# v1.net
KiCad netlist of a schematic drawn in EAGLE
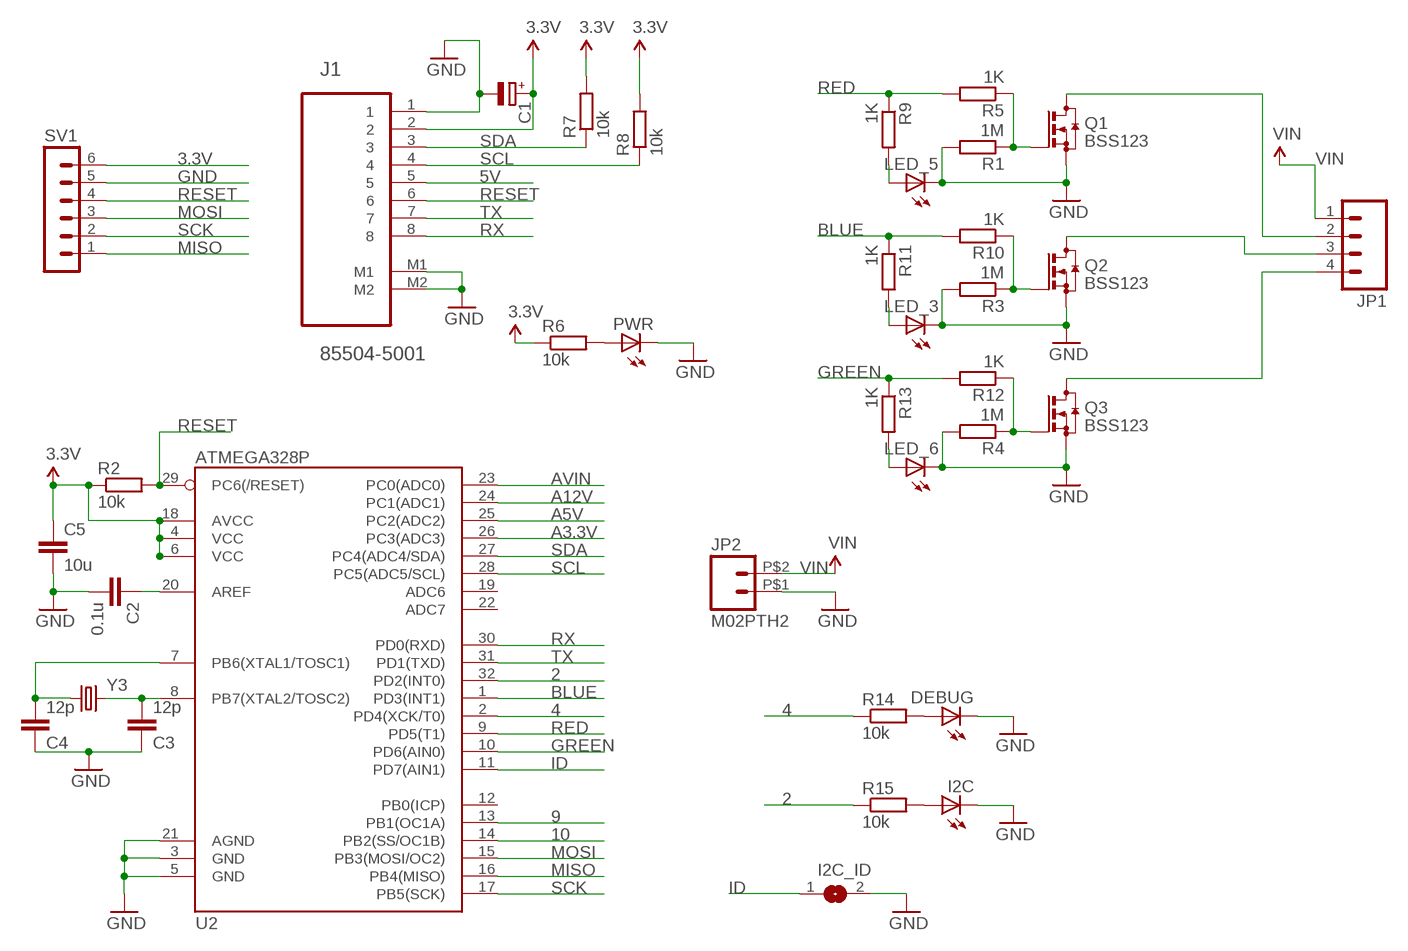
[diagram p0: schematic, sheet 1]

(export (version "E")
  (design (tool "Eeschema 10.0.6"))
  (components
    (comp (ref "C1")
      (value "CPOL-EUE2.5-6")
      (footprint "eagle-import:E2,5-6")
      (libsource (lib "eagle-import") (part "CPOL-EUE2.5-6"))
    )
    (comp (ref "C2")
      (value "0.1u")
      (footprint "eagle-import:C0805")
      (libsource (lib "eagle-import") (part "C-EUC0805"))
    )
    (comp (ref "C3")
      (value "12p")
      (footprint "eagle-import:C0805")
      (libsource (lib "eagle-import") (part "C-EUC0805"))
    )
    (comp (ref "C4")
      (value "12p")
      (footprint "eagle-import:C0805")
      (libsource (lib "eagle-import") (part "C-EUC0805"))
    )
    (comp (ref "C5")
      (value "10u")
      (footprint "eagle-import:C0805")
      (libsource (lib "eagle-import") (part "C-EUC0805"))
    )
    (comp (ref "DEBUG")
      (value "LEDSML0805")
      (footprint "eagle-import:SML0805")
      (libsource (lib "eagle-import") (part "LEDSML0805"))
    )
    (comp (ref "I2C")
      (value "LEDSML0805")
      (footprint "eagle-import:SML0805")
      (libsource (lib "eagle-import") (part "LEDSML0805"))
    )
    (comp (ref "I2C_ID")
      (value "SJ")
      (footprint "eagle-import:SJ")
      (libsource (lib "eagle-import") (part "SJ"))
    )
    (comp (ref "J1")
      (value "85504-5001")
      (footprint "eagle-import:MOLEX_85504-5001")
      (libsource (lib "eagle-import") (part "85504-5001"))
    )
    (comp (ref "JP1")
      (value "M04POLAR")
      (footprint "eagle-import:MOLEX-1X4")
      (libsource (lib "eagle-import") (part "M04POLAR"))
    )
    (comp (ref "JP2")
      (value "M02PTH2")
      (footprint "eagle-import:1X02_BIG")
      (libsource (lib "eagle-import") (part "M02PTH2"))
    )
    (comp (ref "LED_3")
      (value "LEDSML0805")
      (footprint "eagle-import:SML0805")
      (libsource (lib "eagle-import") (part "LEDSML0805"))
    )
    (comp (ref "LED_5")
      (value "LEDSML0805")
      (footprint "eagle-import:SML0805")
      (libsource (lib "eagle-import") (part "LEDSML0805"))
    )
    (comp (ref "LED_6")
      (value "LEDSML0805")
      (footprint "eagle-import:SML0805")
      (libsource (lib "eagle-import") (part "LEDSML0805"))
    )
    (comp (ref "PWR")
      (value "LEDSML0805")
      (footprint "eagle-import:SML0805")
      (libsource (lib "eagle-import") (part "LEDSML0805"))
    )
    (comp (ref "Q1")
      (value "BSS123")
      (footprint "eagle-import:SOT23")
      (libsource (lib "eagle-import") (part "BSS123"))
    )
    (comp (ref "Q2")
      (value "BSS123")
      (footprint "eagle-import:SOT23")
      (libsource (lib "eagle-import") (part "BSS123"))
    )
    (comp (ref "Q3")
      (value "BSS123")
      (footprint "eagle-import:SOT23")
      (libsource (lib "eagle-import") (part "BSS123"))
    )
    (comp (ref "R1")
      (value "1M")
      (footprint "eagle-import:R0805")
      (libsource (lib "eagle-import") (part "R-EU_R0805"))
    )
    (comp (ref "R2")
      (value "10k")
      (footprint "eagle-import:R0805")
      (libsource (lib "eagle-import") (part "R-EU_R0805"))
    )
    (comp (ref "R3")
      (value "1M")
      (footprint "eagle-import:R0805")
      (libsource (lib "eagle-import") (part "R-EU_R0805"))
    )
    (comp (ref "R4")
      (value "1M")
      (footprint "eagle-import:R0805")
      (libsource (lib "eagle-import") (part "R-EU_R0805"))
    )
    (comp (ref "R5")
      (value "1K")
      (footprint "eagle-import:R0805")
      (libsource (lib "eagle-import") (part "R-EU_R0805"))
    )
    (comp (ref "R6")
      (value "10k")
      (footprint "eagle-import:R0805")
      (libsource (lib "eagle-import") (part "R-EU_R0805"))
    )
    (comp (ref "R7")
      (value "10k")
      (footprint "eagle-import:R0805")
      (libsource (lib "eagle-import") (part "R-EU_R0805"))
    )
    (comp (ref "R8")
      (value "10k")
      (footprint "eagle-import:R0805")
      (libsource (lib "eagle-import") (part "R-EU_R0805"))
    )
    (comp (ref "R9")
      (value "1K")
      (footprint "eagle-import:R0805")
      (libsource (lib "eagle-import") (part "R-EU_R0805"))
    )
    (comp (ref "R10")
      (value "1K")
      (footprint "eagle-import:R0805")
      (libsource (lib "eagle-import") (part "R-EU_R0805"))
    )
    (comp (ref "R11")
      (value "1K")
      (footprint "eagle-import:R0805")
      (libsource (lib "eagle-import") (part "R-EU_R0805"))
    )
    (comp (ref "R12")
      (value "1K")
      (footprint "eagle-import:R0805")
      (libsource (lib "eagle-import") (part "R-EU_R0805"))
    )
    (comp (ref "R13")
      (value "1K")
      (footprint "eagle-import:R0805")
      (libsource (lib "eagle-import") (part "R-EU_R0805"))
    )
    (comp (ref "R14")
      (value "10k")
      (footprint "eagle-import:R0805")
      (libsource (lib "eagle-import") (part "R-EU_R0805"))
    )
    (comp (ref "R15")
      (value "10k")
      (footprint "eagle-import:R0805")
      (libsource (lib "eagle-import") (part "R-EU_R0805"))
    )
    (comp (ref "SV1")
      (value "MA06-1")
      (footprint "eagle-import:MA06-1")
      (libsource (lib "eagle-import") (part "MA06-1"))
    )
    (comp (ref "U2")
      (value "ATMEGA328P")
      (footprint "eagle-import:TQFP32-08")
      (libsource (lib "eagle-import") (part "ATMEGA328_SMT"))
    )
    (comp (ref "Y3")
      (value "CRYSTALCRYSTAL-SMD-5X3-LARGEPAD")
      (footprint "eagle-import:CRYSTAL-SMD-5X3")
      (libsource (lib "eagle-import") (part "CRYSTALCRYSTAL-SMD-5X3-LARGEPAD"))
    )
  )
  (nets
    (net (code "1") (name "/2") (class "Default")
      (node (ref "R15") (pin "1") (pinfunction "1_1") (pintype "passive"))
      (node (ref "U2") (pin "32") (pinfunction "PD2(INT0)_32") (pintype "bidirectional"))
    )
    (net (code "2") (name "/4") (class "Default")
      (node (ref "R14") (pin "1") (pinfunction "1_1") (pintype "passive"))
      (node (ref "U2") (pin "2") (pinfunction "PD4(XCK/T0)_2") (pintype "bidirectional"))
    )
    (net (code "3") (name "/5V") (class "Default")
      (node (ref "J1") (pin "5") (pinfunction "5_5") (pintype "bidirectional"))
    )
    (net (code "4") (name "/9") (class "Default")
      (node (ref "U2") (pin "13") (pinfunction "PB1(OC1A)_13") (pintype "bidirectional"))
    )
    (net (code "5") (name "/10") (class "Default")
      (node (ref "U2") (pin "14") (pinfunction "PB2(SS/OC1B)_14") (pintype "bidirectional"))
    )
    (net (code "6") (name "/A3.3V") (class "Default")
      (node (ref "U2") (pin "26") (pinfunction "PC3(ADC3)_26") (pintype "bidirectional"))
    )
    (net (code "7") (name "/A5V") (class "Default")
      (node (ref "U2") (pin "25") (pinfunction "PC2(ADC2)_25") (pintype "bidirectional"))
    )
    (net (code "8") (name "/A12V") (class "Default")
      (node (ref "U2") (pin "24") (pinfunction "PC1(ADC1)_24") (pintype "bidirectional"))
    )
    (net (code "9") (name "/AVIN") (class "Default")
      (node (ref "U2") (pin "23") (pinfunction "PC0(ADC0)_23") (pintype "bidirectional"))
    )
    (net (code "10") (name "/BLUE") (class "Default")
      (node (ref "R10") (pin "2") (pinfunction "2_2") (pintype "passive"))
      (node (ref "R11") (pin "1") (pinfunction "1_1") (pintype "passive"))
      (node (ref "U2") (pin "1") (pinfunction "PD3(INT1)_1") (pintype "bidirectional"))
    )
    (net (code "11") (name "/GREEN") (class "Default")
      (node (ref "R12") (pin "2") (pinfunction "2_2") (pintype "passive"))
      (node (ref "R13") (pin "1") (pinfunction "1_1") (pintype "passive"))
      (node (ref "U2") (pin "10") (pinfunction "PD6(AIN0)_10") (pintype "bidirectional"))
    )
    (net (code "12") (name "/ID") (class "Default")
      (node (ref "I2C_ID") (pin "1") (pinfunction "1_1") (pintype "passive"))
      (node (ref "U2") (pin "11") (pinfunction "PD7(AIN1)_11") (pintype "bidirectional"))
    )
    (net (code "13") (name "/MISO") (class "Default")
      (node (ref "SV1") (pin "1") (pinfunction "1_1") (pintype "passive"))
      (node (ref "U2") (pin "16") (pinfunction "PB4(MISO)_16") (pintype "bidirectional"))
    )
    (net (code "14") (name "/MOSI") (class "Default")
      (node (ref "SV1") (pin "3") (pinfunction "3_3") (pintype "passive"))
      (node (ref "U2") (pin "15") (pinfunction "PB3(MOSI/OC2)_15") (pintype "bidirectional"))
    )
    (net (code "15") (name "/RED") (class "Default")
      (node (ref "R5") (pin "2") (pinfunction "2_2") (pintype "passive"))
      (node (ref "R9") (pin "1") (pinfunction "1_1") (pintype "passive"))
      (node (ref "U2") (pin "9") (pinfunction "PD5(T1)_9") (pintype "bidirectional"))
    )
    (net (code "16") (name "/RESET") (class "Default")
      (node (ref "J1") (pin "6") (pinfunction "6_6") (pintype "bidirectional"))
      (node (ref "R2") (pin "2") (pinfunction "2_2") (pintype "passive"))
      (node (ref "SV1") (pin "4") (pinfunction "4_4") (pintype "passive"))
      (node (ref "U2") (pin "29") (pinfunction "PC6(/RESET)_29") (pintype "bidirectional"))
    )
    (net (code "17") (name "/RX") (class "Default")
      (node (ref "J1") (pin "8") (pinfunction "8_8") (pintype "bidirectional"))
      (node (ref "U2") (pin "30") (pinfunction "PD0(RXD)_30") (pintype "bidirectional"))
    )
    (net (code "18") (name "/SCK") (class "Default")
      (node (ref "SV1") (pin "2") (pinfunction "2_2") (pintype "passive"))
      (node (ref "U2") (pin "17") (pinfunction "PB5(SCK)_17") (pintype "bidirectional"))
    )
    (net (code "19") (name "/SCL") (class "Default")
      (node (ref "J1") (pin "4") (pinfunction "4_4") (pintype "bidirectional"))
      (node (ref "R8") (pin "1") (pinfunction "1_1") (pintype "passive"))
      (node (ref "U2") (pin "28") (pinfunction "PC5(ADC5/SCL)_28") (pintype "bidirectional"))
    )
    (net (code "20") (name "/SDA") (class "Default")
      (node (ref "J1") (pin "3") (pinfunction "3_3") (pintype "bidirectional"))
      (node (ref "R7") (pin "1") (pinfunction "1_1") (pintype "passive"))
      (node (ref "U2") (pin "27") (pinfunction "PC4(ADC4/SDA)_27") (pintype "bidirectional"))
    )
    (net (code "21") (name "/TX") (class "Default")
      (node (ref "J1") (pin "7") (pinfunction "7_7") (pintype "bidirectional"))
      (node (ref "U2") (pin "31") (pinfunction "PD1(TXD)_31") (pintype "bidirectional"))
    )
    (net (code "22") (name "3.3V") (class "Default")
      (node (ref "C1") (pin "+") (pinfunction "+_+") (pintype "passive"))
      (node (ref "C5") (pin "1") (pinfunction "1_1") (pintype "passive"))
      (node (ref "J1") (pin "2") (pinfunction "2_2") (pintype "bidirectional"))
      (node (ref "R2") (pin "1") (pinfunction "1_1") (pintype "passive"))
      (node (ref "R6") (pin "1") (pinfunction "1_1") (pintype "passive"))
      (node (ref "R7") (pin "2") (pinfunction "2_2") (pintype "passive"))
      (node (ref "R8") (pin "2") (pinfunction "2_2") (pintype "passive"))
      (node (ref "SV1") (pin "6") (pinfunction "6_6") (pintype "passive"))
      (node (ref "U2") (pin "18") (pinfunction "AVCC_18") (pintype "bidirectional"))
      (node (ref "U2") (pin "4") (pinfunction "VCC_4") (pintype "bidirectional"))
      (node (ref "U2") (pin "6") (pinfunction "VCC_6") (pintype "bidirectional"))
    )
    (net (code "23") (name "GND") (class "Default")
      (node (ref "C1") (pin "-") (pinfunction "-_-") (pintype "passive"))
      (node (ref "C2") (pin "2") (pinfunction "2_2") (pintype "passive"))
      (node (ref "C3") (pin "1") (pinfunction "1_1") (pintype "passive"))
      (node (ref "C4") (pin "1") (pinfunction "1_1") (pintype "passive"))
      (node (ref "C5") (pin "2") (pinfunction "2_2") (pintype "passive"))
      (node (ref "DEBUG") (pin "C") (pinfunction "C_C") (pintype "passive"))
      (node (ref "I2C") (pin "C") (pinfunction "C_C") (pintype "passive"))
      (node (ref "I2C_ID") (pin "2") (pinfunction "2_2") (pintype "passive"))
      (node (ref "J1") (pin "1") (pinfunction "1_1") (pintype "bidirectional"))
      (node (ref "J1") (pin "M1") (pinfunction "M1_M1") (pintype "bidirectional"))
      (node (ref "J1") (pin "M2") (pinfunction "M2_M2") (pintype "bidirectional"))
      (node (ref "JP2") (pin "P$1") (pinfunction "1_P$1") (pintype "passive"))
      (node (ref "LED_3") (pin "C") (pinfunction "C_C") (pintype "passive"))
      (node (ref "LED_5") (pin "C") (pinfunction "C_C") (pintype "passive"))
      (node (ref "LED_6") (pin "C") (pinfunction "C_C") (pintype "passive"))
      (node (ref "PWR") (pin "C") (pinfunction "C_C") (pintype "passive"))
      (node (ref "Q1") (pin "2") (pinfunction "S_2") (pintype "passive"))
      (node (ref "Q2") (pin "2") (pinfunction "S_2") (pintype "passive"))
      (node (ref "Q3") (pin "2") (pinfunction "S_2") (pintype "passive"))
      (node (ref "R1") (pin "2") (pinfunction "2_2") (pintype "passive"))
      (node (ref "R3") (pin "2") (pinfunction "2_2") (pintype "passive"))
      (node (ref "R4") (pin "2") (pinfunction "2_2") (pintype "passive"))
      (node (ref "SV1") (pin "5") (pinfunction "5_5") (pintype "passive"))
      (node (ref "U2") (pin "21") (pinfunction "AGND_21") (pintype "bidirectional"))
      (node (ref "U2") (pin "3") (pinfunction "GND_3") (pintype "bidirectional"))
      (node (ref "U2") (pin "5") (pinfunction "GND_5") (pintype "bidirectional"))
    )
    (net (code "24") (name "Net-(DEBUG-PadA)") (class "Default")
      (node (ref "DEBUG") (pin "A") (pinfunction "A_A") (pintype "passive"))
      (node (ref "R14") (pin "2") (pinfunction "2_2") (pintype "passive"))
    )
    (net (code "25") (name "Net-(I2C-PadA)") (class "Default")
      (node (ref "I2C") (pin "A") (pinfunction "A_A") (pintype "passive"))
      (node (ref "R15") (pin "2") (pinfunction "2_2") (pintype "passive"))
    )
    (net (code "26") (name "Net-(LED_3-PadA)") (class "Default")
      (node (ref "LED_3") (pin "A") (pinfunction "A_A") (pintype "passive"))
      (node (ref "R11") (pin "2") (pinfunction "2_2") (pintype "passive"))
    )
    (net (code "27") (name "Net-(LED_5-PadA)") (class "Default")
      (node (ref "LED_5") (pin "A") (pinfunction "A_A") (pintype "passive"))
      (node (ref "R9") (pin "2") (pinfunction "2_2") (pintype "passive"))
    )
    (net (code "28") (name "Net-(LED_6-PadA)") (class "Default")
      (node (ref "LED_6") (pin "A") (pinfunction "A_A") (pintype "passive"))
      (node (ref "R13") (pin "2") (pinfunction "2_2") (pintype "passive"))
    )
    (net (code "29") (name "Net-(PWR-PadA)") (class "Default")
      (node (ref "PWR") (pin "A") (pinfunction "A_A") (pintype "passive"))
      (node (ref "R6") (pin "2") (pinfunction "2_2") (pintype "passive"))
    )
    (net (code "30") (name "Net-(Q1-D)") (class "Default")
      (node (ref "JP1") (pin "2") (pinfunction "2_2") (pintype "passive"))
      (node (ref "Q1") (pin "3") (pinfunction "D_3") (pintype "passive"))
    )
    (net (code "31") (name "Net-(Q1-G)") (class "Default")
      (node (ref "Q1") (pin "1") (pinfunction "G_1") (pintype "passive"))
      (node (ref "R1") (pin "1") (pinfunction "1_1") (pintype "passive"))
      (node (ref "R5") (pin "1") (pinfunction "1_1") (pintype "passive"))
    )
    (net (code "32") (name "Net-(Q2-D)") (class "Default")
      (node (ref "JP1") (pin "3") (pinfunction "3_3") (pintype "passive"))
      (node (ref "Q2") (pin "3") (pinfunction "D_3") (pintype "passive"))
    )
    (net (code "33") (name "Net-(Q2-G)") (class "Default")
      (node (ref "Q2") (pin "1") (pinfunction "G_1") (pintype "passive"))
      (node (ref "R10") (pin "1") (pinfunction "1_1") (pintype "passive"))
      (node (ref "R3") (pin "1") (pinfunction "1_1") (pintype "passive"))
    )
    (net (code "34") (name "Net-(Q3-D)") (class "Default")
      (node (ref "JP1") (pin "4") (pinfunction "4_4") (pintype "passive"))
      (node (ref "Q3") (pin "3") (pinfunction "D_3") (pintype "passive"))
    )
    (net (code "35") (name "Net-(Q3-G)") (class "Default")
      (node (ref "Q3") (pin "1") (pinfunction "G_1") (pintype "passive"))
      (node (ref "R12") (pin "1") (pinfunction "1_1") (pintype "passive"))
      (node (ref "R4") (pin "1") (pinfunction "1_1") (pintype "passive"))
    )
    (net (code "36") (name "Net-(U2-AREF)") (class "Default")
      (node (ref "C2") (pin "1") (pinfunction "1_1") (pintype "passive"))
      (node (ref "U2") (pin "20") (pinfunction "AREF_20") (pintype "bidirectional"))
    )
    (net (code "37") (name "Net-(U2-PB6(XTAL1{slash}TOSC1))") (class "Default")
      (node (ref "C4") (pin "2") (pinfunction "2_2") (pintype "passive"))
      (node (ref "U2") (pin "7") (pinfunction "PB6(XTAL1/TOSC1)_7") (pintype "bidirectional"))
      (node (ref "Y3") (pin "1") (pinfunction "1_1") (pintype "passive"))
    )
    (net (code "38") (name "Net-(U2-PB7(XTAL2{slash}TOSC2))") (class "Default")
      (node (ref "C3") (pin "2") (pinfunction "2_2") (pintype "passive"))
      (node (ref "U2") (pin "8") (pinfunction "PB7(XTAL2/TOSC2)_8") (pintype "bidirectional"))
      (node (ref "Y3") (pin "3") (pinfunction "2_3") (pintype "passive"))
    )
    (net (code "39") (name "VIN") (class "Default")
      (node (ref "JP1") (pin "1") (pinfunction "1_1") (pintype "passive"))
      (node (ref "JP2") (pin "P$2") (pinfunction "2_P$2") (pintype "passive"))
    )
    (net (code "40") (name "unconnected-(U2-ADC6-Pad19)") (class "Default")
      (node (ref "U2") (pin "19") (pinfunction "ADC6_19") (pintype "bidirectional"))
    )
    (net (code "41") (name "unconnected-(U2-ADC7-Pad22)") (class "Default")
      (node (ref "U2") (pin "22") (pinfunction "ADC7_22") (pintype "bidirectional"))
    )
    (net (code "42") (name "unconnected-(U2-PB0(ICP)-Pad12)") (class "Default")
      (node (ref "U2") (pin "12") (pinfunction "PB0(ICP)_12") (pintype "bidirectional"))
    )
  )
)
